# Hauptstation.net
KiCad netlist of a schematic drawn in EAGLE
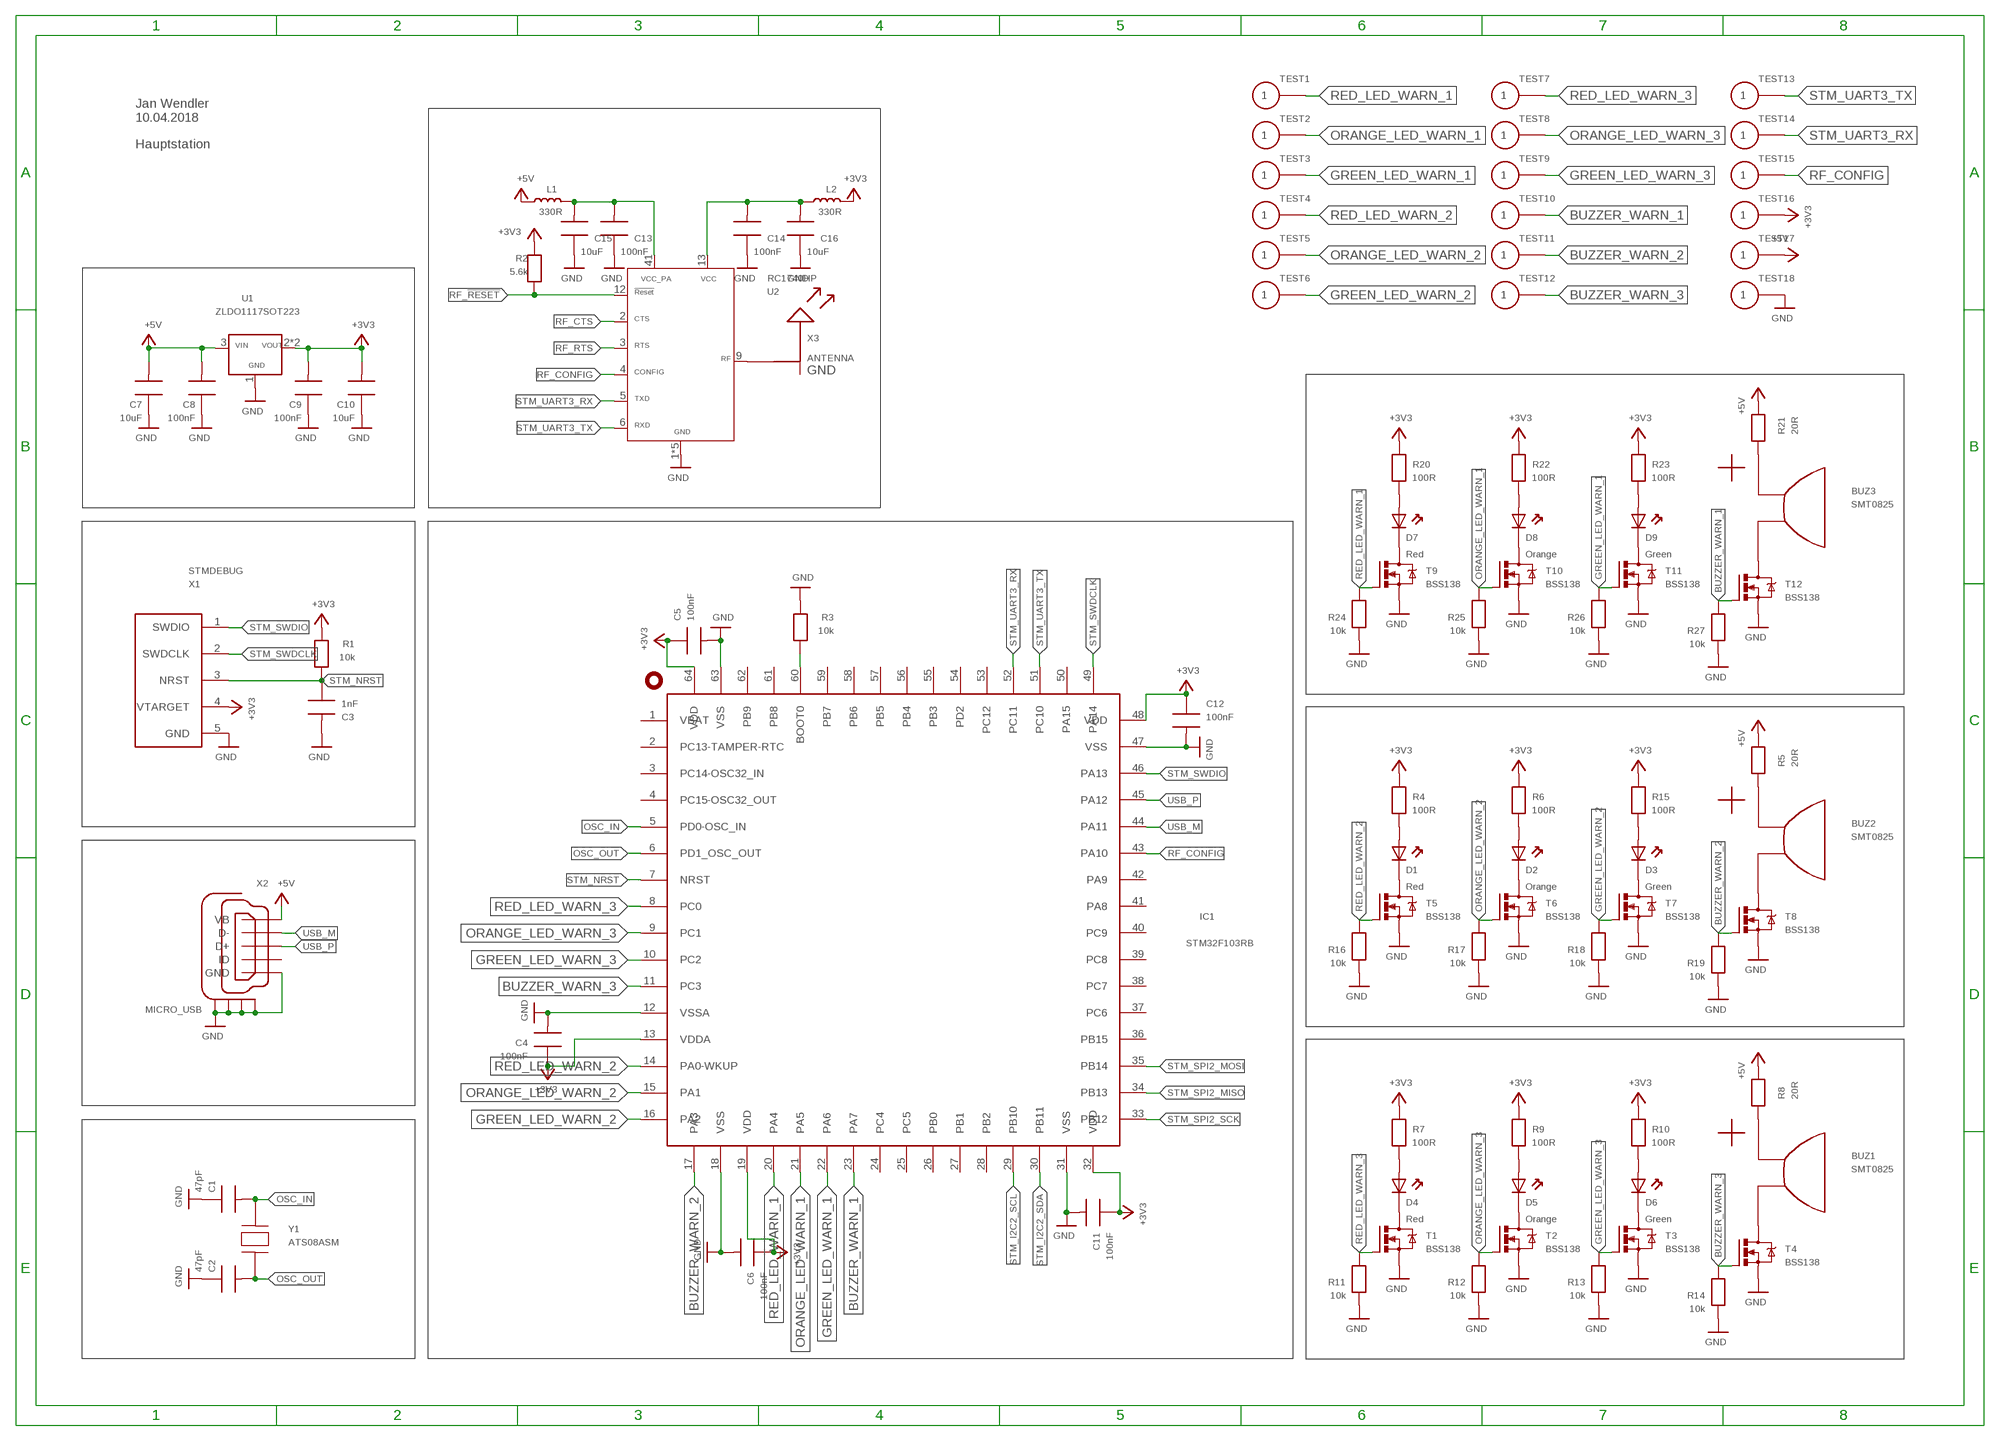
[diagram p0: schematic, sheet 1]

(export (version "E")
  (design (tool "Eeschema 10.0.6"))
  (components
    (comp (ref "BUZ1")
      (value "SMT0825")
      (footprint "eagle-import:SMT0825")
      (libsource (lib "eagle-import") (part "SMT0825"))
    )
    (comp (ref "BUZ2")
      (value "SMT0825")
      (footprint "eagle-import:SMT0825")
      (libsource (lib "eagle-import") (part "SMT0825"))
    )
    (comp (ref "BUZ3")
      (value "SMT0825")
      (footprint "eagle-import:SMT0825")
      (libsource (lib "eagle-import") (part "SMT0825"))
    )
    (comp (ref "C1")
      (value "47pF")
      (footprint "eagle-import:0603")
      (libsource (lib "eagle-import") (part "C0603"))
    )
    (comp (ref "C2")
      (value "47pF")
      (footprint "eagle-import:0603")
      (libsource (lib "eagle-import") (part "C0603"))
    )
    (comp (ref "C3")
      (value "1nF")
      (footprint "eagle-import:0603")
      (libsource (lib "eagle-import") (part "C0603"))
    )
    (comp (ref "C4")
      (value "100nF")
      (footprint "eagle-import:0603")
      (libsource (lib "eagle-import") (part "C0603"))
    )
    (comp (ref "C5")
      (value "100nF")
      (footprint "eagle-import:0603")
      (libsource (lib "eagle-import") (part "C0603"))
    )
    (comp (ref "C6")
      (value "100nF")
      (footprint "eagle-import:0603")
      (libsource (lib "eagle-import") (part "C0603"))
    )
    (comp (ref "C7")
      (value "10uF")
      (footprint "eagle-import:0603")
      (libsource (lib "eagle-import") (part "C0603"))
    )
    (comp (ref "C8")
      (value "100nF")
      (footprint "eagle-import:0603")
      (libsource (lib "eagle-import") (part "C0603"))
    )
    (comp (ref "C9")
      (value "100nF")
      (footprint "eagle-import:0603")
      (libsource (lib "eagle-import") (part "C0603"))
    )
    (comp (ref "C10")
      (value "10uF")
      (footprint "eagle-import:0603")
      (libsource (lib "eagle-import") (part "C0603"))
    )
    (comp (ref "C11")
      (value "100nF")
      (footprint "eagle-import:0603")
      (libsource (lib "eagle-import") (part "C0603"))
    )
    (comp (ref "C12")
      (value "100nF")
      (footprint "eagle-import:0603")
      (libsource (lib "eagle-import") (part "C0603"))
    )
    (comp (ref "C13")
      (value "100nF")
      (footprint "eagle-import:0603")
      (libsource (lib "eagle-import") (part "C0603"))
    )
    (comp (ref "C14")
      (value "100nF")
      (footprint "eagle-import:0603")
      (libsource (lib "eagle-import") (part "C0603"))
    )
    (comp (ref "C15")
      (value "10uF")
      (footprint "eagle-import:0603")
      (libsource (lib "eagle-import") (part "C0603"))
    )
    (comp (ref "C16")
      (value "10uF")
      (footprint "eagle-import:0603")
      (libsource (lib "eagle-import") (part "C0603"))
    )
    (comp (ref "D1")
      (value "Red")
      (footprint "eagle-import:0603")
      (libsource (lib "eagle-import") (part "D0603"))
    )
    (comp (ref "D2")
      (value "Orange")
      (footprint "eagle-import:0603")
      (libsource (lib "eagle-import") (part "D0603"))
    )
    (comp (ref "D3")
      (value "Green")
      (footprint "eagle-import:0603")
      (libsource (lib "eagle-import") (part "D0603"))
    )
    (comp (ref "D4")
      (value "Red")
      (footprint "eagle-import:0603")
      (libsource (lib "eagle-import") (part "D0603"))
    )
    (comp (ref "D5")
      (value "Orange")
      (footprint "eagle-import:0603")
      (libsource (lib "eagle-import") (part "D0603"))
    )
    (comp (ref "D6")
      (value "Green")
      (footprint "eagle-import:0603")
      (libsource (lib "eagle-import") (part "D0603"))
    )
    (comp (ref "D7")
      (value "Red")
      (footprint "eagle-import:0603")
      (libsource (lib "eagle-import") (part "D0603"))
    )
    (comp (ref "D8")
      (value "Orange")
      (footprint "eagle-import:0603")
      (libsource (lib "eagle-import") (part "D0603"))
    )
    (comp (ref "D9")
      (value "Green")
      (footprint "eagle-import:0603")
      (libsource (lib "eagle-import") (part "D0603"))
    )
    (comp (ref "IC1")
      (value "STM32F103RB")
      (footprint "eagle-import:LQFP64")
      (libsource (lib "eagle-import") (part "STM32F103RB"))
    )
    (comp (ref "L1")
      (value "330R")
      (footprint "eagle-import:0603")
      (libsource (lib "eagle-import") (part "L0603"))
    )
    (comp (ref "L2")
      (value "330R")
      (footprint "eagle-import:0603")
      (libsource (lib "eagle-import") (part "L0603"))
    )
    (comp (ref "R1")
      (value "10k")
      (footprint "eagle-import:0603")
      (libsource (lib "eagle-import") (part "R0603"))
    )
    (comp (ref "R2")
      (value "5.6k")
      (footprint "eagle-import:0603")
      (libsource (lib "eagle-import") (part "R0603"))
    )
    (comp (ref "R3")
      (value "10k")
      (footprint "eagle-import:0603")
      (libsource (lib "eagle-import") (part "R0603"))
    )
    (comp (ref "R4")
      (value "100R")
      (footprint "eagle-import:0603")
      (libsource (lib "eagle-import") (part "R0603"))
    )
    (comp (ref "R5")
      (value "20R")
      (footprint "eagle-import:0603")
      (libsource (lib "eagle-import") (part "R0603"))
    )
    (comp (ref "R6")
      (value "100R")
      (footprint "eagle-import:0603")
      (libsource (lib "eagle-import") (part "R0603"))
    )
    (comp (ref "R7")
      (value "100R")
      (footprint "eagle-import:0603")
      (libsource (lib "eagle-import") (part "R0603"))
    )
    (comp (ref "R8")
      (value "20R")
      (footprint "eagle-import:0603")
      (libsource (lib "eagle-import") (part "R0603"))
    )
    (comp (ref "R9")
      (value "100R")
      (footprint "eagle-import:0603")
      (libsource (lib "eagle-import") (part "R0603"))
    )
    (comp (ref "R10")
      (value "100R")
      (footprint "eagle-import:0603")
      (libsource (lib "eagle-import") (part "R0603"))
    )
    (comp (ref "R11")
      (value "10k")
      (footprint "eagle-import:0603")
      (libsource (lib "eagle-import") (part "R0603"))
    )
    (comp (ref "R12")
      (value "10k")
      (footprint "eagle-import:0603")
      (libsource (lib "eagle-import") (part "R0603"))
    )
    (comp (ref "R13")
      (value "10k")
      (footprint "eagle-import:0603")
      (libsource (lib "eagle-import") (part "R0603"))
    )
    (comp (ref "R14")
      (value "10k")
      (footprint "eagle-import:0603")
      (libsource (lib "eagle-import") (part "R0603"))
    )
    (comp (ref "R15")
      (value "100R")
      (footprint "eagle-import:0603")
      (libsource (lib "eagle-import") (part "R0603"))
    )
    (comp (ref "R16")
      (value "10k")
      (footprint "eagle-import:0603")
      (libsource (lib "eagle-import") (part "R0603"))
    )
    (comp (ref "R17")
      (value "10k")
      (footprint "eagle-import:0603")
      (libsource (lib "eagle-import") (part "R0603"))
    )
    (comp (ref "R18")
      (value "10k")
      (footprint "eagle-import:0603")
      (libsource (lib "eagle-import") (part "R0603"))
    )
    (comp (ref "R19")
      (value "10k")
      (footprint "eagle-import:0603")
      (libsource (lib "eagle-import") (part "R0603"))
    )
    (comp (ref "R20")
      (value "100R")
      (footprint "eagle-import:0603")
      (libsource (lib "eagle-import") (part "R0603"))
    )
    (comp (ref "R21")
      (value "20R")
      (footprint "eagle-import:0603")
      (libsource (lib "eagle-import") (part "R0603"))
    )
    (comp (ref "R22")
      (value "100R")
      (footprint "eagle-import:0603")
      (libsource (lib "eagle-import") (part "R0603"))
    )
    (comp (ref "R23")
      (value "100R")
      (footprint "eagle-import:0603")
      (libsource (lib "eagle-import") (part "R0603"))
    )
    (comp (ref "R24")
      (value "10k")
      (footprint "eagle-import:0603")
      (libsource (lib "eagle-import") (part "R0603"))
    )
    (comp (ref "R25")
      (value "10k")
      (footprint "eagle-import:0603")
      (libsource (lib "eagle-import") (part "R0603"))
    )
    (comp (ref "R26")
      (value "10k")
      (footprint "eagle-import:0603")
      (libsource (lib "eagle-import") (part "R0603"))
    )
    (comp (ref "R27")
      (value "10k")
      (footprint "eagle-import:0603")
      (libsource (lib "eagle-import") (part "R0603"))
    )
    (comp (ref "T1")
      (value "BSS138")
      (footprint "eagle-import:SOT23")
      (libsource (lib "eagle-import") (part "BSS138"))
    )
    (comp (ref "T2")
      (value "BSS138")
      (footprint "eagle-import:SOT23")
      (libsource (lib "eagle-import") (part "BSS138"))
    )
    (comp (ref "T3")
      (value "BSS138")
      (footprint "eagle-import:SOT23")
      (libsource (lib "eagle-import") (part "BSS138"))
    )
    (comp (ref "T4")
      (value "BSS138")
      (footprint "eagle-import:SOT23")
      (libsource (lib "eagle-import") (part "BSS138"))
    )
    (comp (ref "T5")
      (value "BSS138")
      (footprint "eagle-import:SOT23")
      (libsource (lib "eagle-import") (part "BSS138"))
    )
    (comp (ref "T6")
      (value "BSS138")
      (footprint "eagle-import:SOT23")
      (libsource (lib "eagle-import") (part "BSS138"))
    )
    (comp (ref "T7")
      (value "BSS138")
      (footprint "eagle-import:SOT23")
      (libsource (lib "eagle-import") (part "BSS138"))
    )
    (comp (ref "T8")
      (value "BSS138")
      (footprint "eagle-import:SOT23")
      (libsource (lib "eagle-import") (part "BSS138"))
    )
    (comp (ref "T9")
      (value "BSS138")
      (footprint "eagle-import:SOT23")
      (libsource (lib "eagle-import") (part "BSS138"))
    )
    (comp (ref "T10")
      (value "BSS138")
      (footprint "eagle-import:SOT23")
      (libsource (lib "eagle-import") (part "BSS138"))
    )
    (comp (ref "T11")
      (value "BSS138")
      (footprint "eagle-import:SOT23")
      (libsource (lib "eagle-import") (part "BSS138"))
    )
    (comp (ref "T12")
      (value "BSS138")
      (footprint "eagle-import:SOT23")
      (libsource (lib "eagle-import") (part "BSS138"))
    )
    (comp (ref "TEST1")
      (value "TESTPIN")
      (footprint "eagle-import:TESTPIN")
      (libsource (lib "eagle-import") (part "TESTPIN"))
    )
    (comp (ref "TEST2")
      (value "TESTPIN")
      (footprint "eagle-import:TESTPIN")
      (libsource (lib "eagle-import") (part "TESTPIN"))
    )
    (comp (ref "TEST3")
      (value "TESTPIN")
      (footprint "eagle-import:TESTPIN")
      (libsource (lib "eagle-import") (part "TESTPIN"))
    )
    (comp (ref "TEST4")
      (value "TESTPIN")
      (footprint "eagle-import:TESTPIN")
      (libsource (lib "eagle-import") (part "TESTPIN"))
    )
    (comp (ref "TEST5")
      (value "TESTPIN")
      (footprint "eagle-import:TESTPIN")
      (libsource (lib "eagle-import") (part "TESTPIN"))
    )
    (comp (ref "TEST6")
      (value "TESTPIN")
      (footprint "eagle-import:TESTPIN")
      (libsource (lib "eagle-import") (part "TESTPIN"))
    )
    (comp (ref "TEST7")
      (value "TESTPIN")
      (footprint "eagle-import:TESTPIN")
      (libsource (lib "eagle-import") (part "TESTPIN"))
    )
    (comp (ref "TEST8")
      (value "TESTPIN")
      (footprint "eagle-import:TESTPIN")
      (libsource (lib "eagle-import") (part "TESTPIN"))
    )
    (comp (ref "TEST9")
      (value "TESTPIN")
      (footprint "eagle-import:TESTPIN")
      (libsource (lib "eagle-import") (part "TESTPIN"))
    )
    (comp (ref "TEST10")
      (value "TESTPIN")
      (footprint "eagle-import:TESTPIN")
      (libsource (lib "eagle-import") (part "TESTPIN"))
    )
    (comp (ref "TEST11")
      (value "TESTPIN")
      (footprint "eagle-import:TESTPIN")
      (libsource (lib "eagle-import") (part "TESTPIN"))
    )
    (comp (ref "TEST12")
      (value "TESTPIN")
      (footprint "eagle-import:TESTPIN")
      (libsource (lib "eagle-import") (part "TESTPIN"))
    )
    (comp (ref "TEST13")
      (value "TESTPIN")
      (footprint "eagle-import:TESTPIN")
      (libsource (lib "eagle-import") (part "TESTPIN"))
    )
    (comp (ref "TEST14")
      (value "TESTPIN")
      (footprint "eagle-import:TESTPIN")
      (libsource (lib "eagle-import") (part "TESTPIN"))
    )
    (comp (ref "TEST15")
      (value "TESTPIN")
      (footprint "eagle-import:TESTPIN")
      (libsource (lib "eagle-import") (part "TESTPIN"))
    )
    (comp (ref "TEST16")
      (value "TESTPIN")
      (footprint "eagle-import:TESTPIN")
      (libsource (lib "eagle-import") (part "TESTPIN"))
    )
    (comp (ref "TEST17")
      (value "TESTPIN")
      (footprint "eagle-import:TESTPIN")
      (libsource (lib "eagle-import") (part "TESTPIN"))
    )
    (comp (ref "TEST18")
      (value "TESTPIN")
      (footprint "eagle-import:TESTPIN")
      (libsource (lib "eagle-import") (part "TESTPIN"))
    )
    (comp (ref "U1")
      (value "ZLDO1117SOT223")
      (footprint "eagle-import:SOT223")
      (libsource (lib "eagle-import") (part "ZLDO1117SOT223"))
    )
    (comp (ref "U2")
      (value "RC1740HP")
      (footprint "eagle-import:RADIOCRAFTS_MODULE")
      (libsource (lib "eagle-import") (part "RC1740HP"))
    )
    (comp (ref "X1")
      (value "STMDEBUG")
      (footprint "eagle-import:STIFTLEISTE1X5")
      (libsource (lib "eagle-import") (part "STMDEBUG"))
    )
    (comp (ref "X2")
      (value "MICRO_USB")
      (footprint "eagle-import:MICRO-USB")
      (libsource (lib "eagle-import") (part "MICRO_USB"))
    )
    (comp (ref "X3")
      (value "ANTENNA")
      (footprint "eagle-import:ANTENNE_CON")
      (libsource (lib "eagle-import") (part "ANTENNA"))
    )
    (comp (ref "Y1")
      (value "ATS08ASM")
      (footprint "eagle-import:HC49_US")
      (libsource (lib "eagle-import") (part "ATS08ASM"))
    )
  )
  (nets
    (net (code "1") (name "+3V3") (class "Default")
      (node (ref "C10") (pin "1") (pinfunction "P$1_1") (pintype "bidirectional"))
      (node (ref "C11") (pin "2") (pinfunction "P$2_2") (pintype "bidirectional"))
      (node (ref "C12") (pin "2") (pinfunction "P$2_2") (pintype "bidirectional"))
      (node (ref "C4") (pin "2") (pinfunction "P$2_2") (pintype "bidirectional"))
      (node (ref "C5") (pin "2") (pinfunction "P$2_2") (pintype "bidirectional"))
      (node (ref "C6") (pin "2") (pinfunction "P$2_2") (pintype "bidirectional"))
      (node (ref "C9") (pin "1") (pinfunction "P$1_1") (pintype "bidirectional"))
      (node (ref "IC1") (pin "13") (pinfunction "VDDA_13") (pintype "bidirectional"))
      (node (ref "IC1") (pin "19") (pinfunction "VDD_19") (pintype "bidirectional"))
      (node (ref "IC1") (pin "32") (pinfunction "VDD_32") (pintype "bidirectional"))
      (node (ref "IC1") (pin "48") (pinfunction "VDD_48") (pintype "bidirectional"))
      (node (ref "IC1") (pin "64") (pinfunction "VDD_64") (pintype "bidirectional"))
      (node (ref "L2") (pin "1") (pinfunction "P$1_1") (pintype "bidirectional"))
      (node (ref "R1") (pin "2") (pinfunction "P$2_2") (pintype "bidirectional"))
      (node (ref "R10") (pin "2") (pinfunction "P$2_2") (pintype "bidirectional"))
      (node (ref "R15") (pin "2") (pinfunction "P$2_2") (pintype "bidirectional"))
      (node (ref "R2") (pin "2") (pinfunction "P$2_2") (pintype "bidirectional"))
      (node (ref "R20") (pin "2") (pinfunction "P$2_2") (pintype "bidirectional"))
      (node (ref "R22") (pin "2") (pinfunction "P$2_2") (pintype "bidirectional"))
      (node (ref "R23") (pin "2") (pinfunction "P$2_2") (pintype "bidirectional"))
      (node (ref "R4") (pin "2") (pinfunction "P$2_2") (pintype "bidirectional"))
      (node (ref "R6") (pin "2") (pinfunction "P$2_2") (pintype "bidirectional"))
      (node (ref "R7") (pin "2") (pinfunction "P$2_2") (pintype "bidirectional"))
      (node (ref "R9") (pin "2") (pinfunction "P$2_2") (pintype "bidirectional"))
      (node (ref "TEST16") (pin "1") (pinfunction "1_1") (pintype "bidirectional"))
      (node (ref "U1") (pin "2") (pinfunction "VOUT_2") (pintype "bidirectional"))
      (node (ref "U1") (pin "PAD") (pinfunction "VOUT_PAD") (pintype "bidirectional"))
      (node (ref "X1") (pin "4") (pinfunction "VTARGET_4") (pintype "bidirectional"))
    )
    (net (code "2") (name "+5V") (class "Default")
      (node (ref "C7") (pin "1") (pinfunction "P$1_1") (pintype "bidirectional"))
      (node (ref "C8") (pin "1") (pinfunction "P$1_1") (pintype "bidirectional"))
      (node (ref "L1") (pin "2") (pinfunction "P$2_2") (pintype "bidirectional"))
      (node (ref "R21") (pin "2") (pinfunction "P$2_2") (pintype "bidirectional"))
      (node (ref "R5") (pin "2") (pinfunction "P$2_2") (pintype "bidirectional"))
      (node (ref "R8") (pin "2") (pinfunction "P$2_2") (pintype "bidirectional"))
      (node (ref "TEST17") (pin "1") (pinfunction "1_1") (pintype "bidirectional"))
      (node (ref "U1") (pin "3") (pinfunction "VIN_3") (pintype "bidirectional"))
      (node (ref "X2") (pin "1") (pinfunction "VB_1") (pintype "passive"))
    )
    (net (code "3") (name "/RF_~{RESET}") (class "Default")
      (node (ref "R2") (pin "1") (pinfunction "P$1_1") (pintype "bidirectional"))
      (node (ref "U2") (pin "12") (pinfunction "~{RESET}_12") (pintype "bidirectional"))
    )
    (net (code "4") (name "BUZZER_WARN_1") (class "Default")
      (node (ref "IC1") (pin "23") (pinfunction "PA7_23") (pintype "bidirectional"))
      (node (ref "R27") (pin "2") (pinfunction "P$2_2") (pintype "bidirectional"))
      (node (ref "T12") (pin "1") (pinfunction "G_1") (pintype "passive"))
      (node (ref "TEST10") (pin "1") (pinfunction "1_1") (pintype "bidirectional"))
    )
    (net (code "5") (name "BUZZER_WARN_2") (class "Default")
      (node (ref "IC1") (pin "17") (pinfunction "PA3_17") (pintype "bidirectional"))
      (node (ref "R19") (pin "2") (pinfunction "P$2_2") (pintype "bidirectional"))
      (node (ref "T8") (pin "1") (pinfunction "G_1") (pintype "passive"))
      (node (ref "TEST11") (pin "1") (pinfunction "1_1") (pintype "bidirectional"))
    )
    (net (code "6") (name "BUZZER_WARN_3") (class "Default")
      (node (ref "IC1") (pin "11") (pinfunction "PC3_11") (pintype "bidirectional"))
      (node (ref "R14") (pin "2") (pinfunction "P$2_2") (pintype "bidirectional"))
      (node (ref "T4") (pin "1") (pinfunction "G_1") (pintype "passive"))
      (node (ref "TEST12") (pin "1") (pinfunction "1_1") (pintype "bidirectional"))
    )
    (net (code "7") (name "GND") (class "Default")
      (node (ref "C1") (pin "2") (pinfunction "P$2_2") (pintype "bidirectional"))
      (node (ref "C10") (pin "2") (pinfunction "P$2_2") (pintype "bidirectional"))
      (node (ref "C11") (pin "1") (pinfunction "P$1_1") (pintype "bidirectional"))
      (node (ref "C12") (pin "1") (pinfunction "P$1_1") (pintype "bidirectional"))
      (node (ref "C13") (pin "2") (pinfunction "P$2_2") (pintype "bidirectional"))
      (node (ref "C14") (pin "2") (pinfunction "P$2_2") (pintype "bidirectional"))
      (node (ref "C15") (pin "2") (pinfunction "P$2_2") (pintype "bidirectional"))
      (node (ref "C16") (pin "2") (pinfunction "P$2_2") (pintype "bidirectional"))
      (node (ref "C2") (pin "2") (pinfunction "P$2_2") (pintype "bidirectional"))
      (node (ref "C3") (pin "1") (pinfunction "P$1_1") (pintype "bidirectional"))
      (node (ref "C4") (pin "1") (pinfunction "P$1_1") (pintype "bidirectional"))
      (node (ref "C5") (pin "1") (pinfunction "P$1_1") (pintype "bidirectional"))
      (node (ref "C6") (pin "1") (pinfunction "P$1_1") (pintype "bidirectional"))
      (node (ref "C7") (pin "2") (pinfunction "P$2_2") (pintype "bidirectional"))
      (node (ref "C8") (pin "2") (pinfunction "P$2_2") (pintype "bidirectional"))
      (node (ref "C9") (pin "2") (pinfunction "P$2_2") (pintype "bidirectional"))
      (node (ref "IC1") (pin "12") (pinfunction "VSSA_12") (pintype "bidirectional"))
      (node (ref "IC1") (pin "18") (pinfunction "VSS_18") (pintype "bidirectional"))
      (node (ref "IC1") (pin "31") (pinfunction "VSS_31") (pintype "bidirectional"))
      (node (ref "IC1") (pin "47") (pinfunction "VSS_47") (pintype "bidirectional"))
      (node (ref "IC1") (pin "63") (pinfunction "VSS_63") (pintype "bidirectional"))
      (node (ref "R11") (pin "1") (pinfunction "P$1_1") (pintype "bidirectional"))
      (node (ref "R12") (pin "1") (pinfunction "P$1_1") (pintype "bidirectional"))
      (node (ref "R13") (pin "1") (pinfunction "P$1_1") (pintype "bidirectional"))
      (node (ref "R14") (pin "1") (pinfunction "P$1_1") (pintype "bidirectional"))
      (node (ref "R16") (pin "1") (pinfunction "P$1_1") (pintype "bidirectional"))
      (node (ref "R17") (pin "1") (pinfunction "P$1_1") (pintype "bidirectional"))
      (node (ref "R18") (pin "1") (pinfunction "P$1_1") (pintype "bidirectional"))
      (node (ref "R19") (pin "1") (pinfunction "P$1_1") (pintype "bidirectional"))
      (node (ref "R24") (pin "1") (pinfunction "P$1_1") (pintype "bidirectional"))
      (node (ref "R25") (pin "1") (pinfunction "P$1_1") (pintype "bidirectional"))
      (node (ref "R26") (pin "1") (pinfunction "P$1_1") (pintype "bidirectional"))
      (node (ref "R27") (pin "1") (pinfunction "P$1_1") (pintype "bidirectional"))
      (node (ref "R3") (pin "2") (pinfunction "P$2_2") (pintype "bidirectional"))
      (node (ref "T1") (pin "2") (pinfunction "S_2") (pintype "passive"))
      (node (ref "T10") (pin "2") (pinfunction "S_2") (pintype "passive"))
      (node (ref "T11") (pin "2") (pinfunction "S_2") (pintype "passive"))
      (node (ref "T12") (pin "2") (pinfunction "S_2") (pintype "passive"))
      (node (ref "T2") (pin "2") (pinfunction "S_2") (pintype "passive"))
      (node (ref "T3") (pin "2") (pinfunction "S_2") (pintype "passive"))
      (node (ref "T4") (pin "2") (pinfunction "S_2") (pintype "passive"))
      (node (ref "T5") (pin "2") (pinfunction "S_2") (pintype "passive"))
      (node (ref "T6") (pin "2") (pinfunction "S_2") (pintype "passive"))
      (node (ref "T7") (pin "2") (pinfunction "S_2") (pintype "passive"))
      (node (ref "T8") (pin "2") (pinfunction "S_2") (pintype "passive"))
      (node (ref "T9") (pin "2") (pinfunction "S_2") (pintype "passive"))
      (node (ref "TEST18") (pin "1") (pinfunction "1_1") (pintype "bidirectional"))
      (node (ref "U1") (pin "1") (pinfunction "GND_1") (pintype "bidirectional"))
      (node (ref "U2") (pin "1") (pinfunction "GND_1") (pintype "bidirectional"))
      (node (ref "U2") (pin "10") (pinfunction "GND_10") (pintype "bidirectional"))
      (node (ref "U2") (pin "14") (pinfunction "GND_14") (pintype "bidirectional"))
      (node (ref "U2") (pin "7") (pinfunction "GND_7") (pintype "bidirectional"))
      (node (ref "U2") (pin "8") (pinfunction "GND_8") (pintype "bidirectional"))
      (node (ref "X1") (pin "5") (pinfunction "GND_5") (pintype "bidirectional"))
      (node (ref "X2") (pin "5") (pinfunction "GND_5") (pintype "passive"))
      (node (ref "X2") (pin "GND1") (pinfunction "S1_GND1") (pintype "passive"))
      (node (ref "X2") (pin "GND2") (pinfunction "S2_GND2") (pintype "passive"))
      (node (ref "X2") (pin "GND3") (pinfunction "S3_GND3") (pintype "passive"))
      (node (ref "X2") (pin "GND4") (pinfunction "S4_GND4") (pintype "passive"))
    )
    (net (code "8") (name "GREEN_LED_WARN_1") (class "Default")
      (node (ref "IC1") (pin "22") (pinfunction "PA6_22") (pintype "bidirectional"))
      (node (ref "R26") (pin "2") (pinfunction "P$2_2") (pintype "bidirectional"))
      (node (ref "T11") (pin "1") (pinfunction "G_1") (pintype "passive"))
      (node (ref "TEST3") (pin "1") (pinfunction "1_1") (pintype "bidirectional"))
    )
    (net (code "9") (name "GREEN_LED_WARN_2") (class "Default")
      (node (ref "IC1") (pin "16") (pinfunction "PA2_16") (pintype "bidirectional"))
      (node (ref "R18") (pin "2") (pinfunction "P$2_2") (pintype "bidirectional"))
      (node (ref "T7") (pin "1") (pinfunction "G_1") (pintype "passive"))
      (node (ref "TEST6") (pin "1") (pinfunction "1_1") (pintype "bidirectional"))
    )
    (net (code "10") (name "GREEN_LED_WARN_3") (class "Default")
      (node (ref "IC1") (pin "10") (pinfunction "PC2_10") (pintype "bidirectional"))
      (node (ref "R13") (pin "2") (pinfunction "P$2_2") (pintype "bidirectional"))
      (node (ref "T3") (pin "1") (pinfunction "G_1") (pintype "passive"))
      (node (ref "TEST9") (pin "1") (pinfunction "1_1") (pintype "bidirectional"))
    )
    (net (code "11") (name "Net-(BUZ1-P$1)") (class "Default")
      (node (ref "BUZ1") (pin "+") (pinfunction "P$1_+") (pintype "bidirectional"))
      (node (ref "R8") (pin "1") (pinfunction "P$1_1") (pintype "bidirectional"))
    )
    (net (code "12") (name "Net-(BUZ1-P$2)") (class "Default")
      (node (ref "BUZ1") (pin "-") (pinfunction "P$2_-") (pintype "bidirectional"))
      (node (ref "T4") (pin "3") (pinfunction "D_3") (pintype "passive"))
    )
    (net (code "13") (name "Net-(BUZ2-P$1)") (class "Default")
      (node (ref "BUZ2") (pin "+") (pinfunction "P$1_+") (pintype "bidirectional"))
      (node (ref "R5") (pin "1") (pinfunction "P$1_1") (pintype "bidirectional"))
    )
    (net (code "14") (name "Net-(BUZ2-P$2)") (class "Default")
      (node (ref "BUZ2") (pin "-") (pinfunction "P$2_-") (pintype "bidirectional"))
      (node (ref "T8") (pin "3") (pinfunction "D_3") (pintype "passive"))
    )
    (net (code "15") (name "Net-(BUZ3-P$1)") (class "Default")
      (node (ref "BUZ3") (pin "+") (pinfunction "P$1_+") (pintype "bidirectional"))
      (node (ref "R21") (pin "1") (pinfunction "P$1_1") (pintype "bidirectional"))
    )
    (net (code "16") (name "Net-(BUZ3-P$2)") (class "Default")
      (node (ref "BUZ3") (pin "-") (pinfunction "P$2_-") (pintype "bidirectional"))
      (node (ref "T12") (pin "3") (pinfunction "D_3") (pintype "passive"))
    )
    (net (code "17") (name "Net-(C13-P$1)") (class "Default")
      (node (ref "C13") (pin "1") (pinfunction "P$1_1") (pintype "bidirectional"))
      (node (ref "C15") (pin "1") (pinfunction "P$1_1") (pintype "bidirectional"))
      (node (ref "L1") (pin "1") (pinfunction "P$1_1") (pintype "bidirectional"))
      (node (ref "U2") (pin "41") (pinfunction "VCC_PA_41") (pintype "bidirectional"))
    )
    (net (code "18") (name "Net-(C14-P$1)") (class "Default")
      (node (ref "C14") (pin "1") (pinfunction "P$1_1") (pintype "bidirectional"))
      (node (ref "C16") (pin "1") (pinfunction "P$1_1") (pintype "bidirectional"))
      (node (ref "L2") (pin "2") (pinfunction "P$2_2") (pintype "bidirectional"))
      (node (ref "U2") (pin "13") (pinfunction "VCC_13") (pintype "bidirectional"))
    )
    (net (code "19") (name "Net-(D1-ANODE)") (class "Default")
      (node (ref "D1") (pin "1") (pinfunction "ANODE_1") (pintype "bidirectional"))
      (node (ref "R4") (pin "1") (pinfunction "P$1_1") (pintype "bidirectional"))
    )
    (net (code "20") (name "Net-(D1-KATHODE)") (class "Default")
      (node (ref "D1") (pin "2") (pinfunction "KATHODE_2") (pintype "bidirectional"))
      (node (ref "T5") (pin "3") (pinfunction "D_3") (pintype "passive"))
    )
    (net (code "21") (name "Net-(D2-ANODE)") (class "Default")
      (node (ref "D2") (pin "1") (pinfunction "ANODE_1") (pintype "bidirectional"))
      (node (ref "R6") (pin "1") (pinfunction "P$1_1") (pintype "bidirectional"))
    )
    (net (code "22") (name "Net-(D2-KATHODE)") (class "Default")
      (node (ref "D2") (pin "2") (pinfunction "KATHODE_2") (pintype "bidirectional"))
      (node (ref "T6") (pin "3") (pinfunction "D_3") (pintype "passive"))
    )
    (net (code "23") (name "Net-(D3-ANODE)") (class "Default")
      (node (ref "D3") (pin "1") (pinfunction "ANODE_1") (pintype "bidirectional"))
      (node (ref "R15") (pin "1") (pinfunction "P$1_1") (pintype "bidirectional"))
    )
    (net (code "24") (name "Net-(D3-KATHODE)") (class "Default")
      (node (ref "D3") (pin "2") (pinfunction "KATHODE_2") (pintype "bidirectional"))
      (node (ref "T7") (pin "3") (pinfunction "D_3") (pintype "passive"))
    )
    (net (code "25") (name "Net-(D4-ANODE)") (class "Default")
      (node (ref "D4") (pin "1") (pinfunction "ANODE_1") (pintype "bidirectional"))
      (node (ref "R7") (pin "1") (pinfunction "P$1_1") (pintype "bidirectional"))
    )
    (net (code "26") (name "Net-(D4-KATHODE)") (class "Default")
      (node (ref "D4") (pin "2") (pinfunction "KATHODE_2") (pintype "bidirectional"))
      (node (ref "T1") (pin "3") (pinfunction "D_3") (pintype "passive"))
    )
    (net (code "27") (name "Net-(D5-ANODE)") (class "Default")
      (node (ref "D5") (pin "1") (pinfunction "ANODE_1") (pintype "bidirectional"))
      (node (ref "R9") (pin "1") (pinfunction "P$1_1") (pintype "bidirectional"))
    )
    (net (code "28") (name "Net-(D5-KATHODE)") (class "Default")
      (node (ref "D5") (pin "2") (pinfunction "KATHODE_2") (pintype "bidirectional"))
      (node (ref "T2") (pin "3") (pinfunction "D_3") (pintype "passive"))
    )
    (net (code "29") (name "Net-(D6-ANODE)") (class "Default")
      (node (ref "D6") (pin "1") (pinfunction "ANODE_1") (pintype "bidirectional"))
      (node (ref "R10") (pin "1") (pinfunction "P$1_1") (pintype "bidirectional"))
    )
    (net (code "30") (name "Net-(D6-KATHODE)") (class "Default")
      (node (ref "D6") (pin "2") (pinfunction "KATHODE_2") (pintype "bidirectional"))
      (node (ref "T3") (pin "3") (pinfunction "D_3") (pintype "passive"))
    )
    (net (code "31") (name "Net-(D7-ANODE)") (class "Default")
      (node (ref "D7") (pin "1") (pinfunction "ANODE_1") (pintype "bidirectional"))
      (node (ref "R20") (pin "1") (pinfunction "P$1_1") (pintype "bidirectional"))
    )
    (net (code "32") (name "Net-(D7-KATHODE)") (class "Default")
      (node (ref "D7") (pin "2") (pinfunction "KATHODE_2") (pintype "bidirectional"))
      (node (ref "T9") (pin "3") (pinfunction "D_3") (pintype "passive"))
    )
    (net (code "33") (name "Net-(D8-ANODE)") (class "Default")
      (node (ref "D8") (pin "1") (pinfunction "ANODE_1") (pintype "bidirectional"))
      (node (ref "R22") (pin "1") (pinfunction "P$1_1") (pintype "bidirectional"))
    )
    (net (code "34") (name "Net-(D8-KATHODE)") (class "Default")
      (node (ref "D8") (pin "2") (pinfunction "KATHODE_2") (pintype "bidirectional"))
      (node (ref "T10") (pin "3") (pinfunction "D_3") (pintype "passive"))
    )
    (net (code "35") (name "Net-(D9-ANODE)") (class "Default")
      (node (ref "D9") (pin "1") (pinfunction "ANODE_1") (pintype "bidirectional"))
      (node (ref "R23") (pin "1") (pinfunction "P$1_1") (pintype "bidirectional"))
    )
    (net (code "36") (name "Net-(D9-KATHODE)") (class "Default")
      (node (ref "D9") (pin "2") (pinfunction "KATHODE_2") (pintype "bidirectional"))
      (node (ref "T11") (pin "3") (pinfunction "D_3") (pintype "passive"))
    )
    (net (code "37") (name "Net-(IC1-BOOT0)") (class "Default")
      (node (ref "IC1") (pin "60") (pinfunction "BOOT0_60") (pintype "bidirectional"))
      (node (ref "R3") (pin "1") (pinfunction "P$1_1") (pintype "bidirectional"))
    )
    (net (code "38") (name "Net-(U2-RF)") (class "Default")
      (node (ref "U2") (pin "9") (pinfunction "RF_9") (pintype "bidirectional"))
      (node (ref "X3") (pin "P$1") (pinfunction "P$1_P$1") (pintype "bidirectional"))
    )
    (net (code "39") (name "ORANGE_LED_WARN_1") (class "Default")
      (node (ref "IC1") (pin "21") (pinfunction "PA5_21") (pintype "bidirectional"))
      (node (ref "R25") (pin "2") (pinfunction "P$2_2") (pintype "bidirectional"))
      (node (ref "T10") (pin "1") (pinfunction "G_1") (pintype "passive"))
      (node (ref "TEST2") (pin "1") (pinfunction "1_1") (pintype "bidirectional"))
    )
    (net (code "40") (name "ORANGE_LED_WARN_2") (class "Default")
      (node (ref "IC1") (pin "15") (pinfunction "PA1_15") (pintype "bidirectional"))
      (node (ref "R17") (pin "2") (pinfunction "P$2_2") (pintype "bidirectional"))
      (node (ref "T6") (pin "1") (pinfunction "G_1") (pintype "passive"))
      (node (ref "TEST5") (pin "1") (pinfunction "1_1") (pintype "bidirectional"))
    )
    (net (code "41") (name "ORANGE_LED_WARN_3") (class "Default")
      (node (ref "IC1") (pin "9") (pinfunction "PC1_9") (pintype "bidirectional"))
      (node (ref "R12") (pin "2") (pinfunction "P$2_2") (pintype "bidirectional"))
      (node (ref "T2") (pin "1") (pinfunction "G_1") (pintype "passive"))
      (node (ref "TEST8") (pin "1") (pinfunction "1_1") (pintype "bidirectional"))
    )
    (net (code "42") (name "OSC_IN") (class "Default")
      (node (ref "C1") (pin "1") (pinfunction "P$1_1") (pintype "bidirectional"))
      (node (ref "IC1") (pin "5") (pinfunction "PD0-OSC_IN_5") (pintype "bidirectional"))
      (node (ref "Y1") (pin "1") (pinfunction "P$1_1") (pintype "bidirectional"))
    )
    (net (code "43") (name "OSC_OUT") (class "Default")
      (node (ref "C2") (pin "1") (pinfunction "P$1_1") (pintype "bidirectional"))
      (node (ref "IC1") (pin "6") (pinfunction "PD1_OSC_OUT_6") (pintype "bidirectional"))
      (node (ref "Y1") (pin "2") (pinfunction "P$2_2") (pintype "bidirectional"))
    )
    (net (code "44") (name "RED_LED_WARN_1") (class "Default")
      (node (ref "IC1") (pin "20") (pinfunction "PA4_20") (pintype "bidirectional"))
      (node (ref "R24") (pin "2") (pinfunction "P$2_2") (pintype "bidirectional"))
      (node (ref "T9") (pin "1") (pinfunction "G_1") (pintype "passive"))
      (node (ref "TEST1") (pin "1") (pinfunction "1_1") (pintype "bidirectional"))
    )
    (net (code "45") (name "RED_LED_WARN_2") (class "Default")
      (node (ref "IC1") (pin "14") (pinfunction "PA0-WKUP_14") (pintype "bidirectional"))
      (node (ref "R16") (pin "2") (pinfunction "P$2_2") (pintype "bidirectional"))
      (node (ref "T5") (pin "1") (pinfunction "G_1") (pintype "passive"))
      (node (ref "TEST4") (pin "1") (pinfunction "1_1") (pintype "bidirectional"))
    )
    (net (code "46") (name "RED_LED_WARN_3") (class "Default")
      (node (ref "IC1") (pin "8") (pinfunction "PC0_8") (pintype "bidirectional"))
      (node (ref "R11") (pin "2") (pinfunction "P$2_2") (pintype "bidirectional"))
      (node (ref "T1") (pin "1") (pinfunction "G_1") (pintype "passive"))
      (node (ref "TEST7") (pin "1") (pinfunction "1_1") (pintype "bidirectional"))
    )
    (net (code "47") (name "RF_CONFIG") (class "Default")
      (node (ref "IC1") (pin "43") (pinfunction "PA10_43") (pintype "bidirectional"))
      (node (ref "TEST15") (pin "1") (pinfunction "1_1") (pintype "bidirectional"))
      (node (ref "U2") (pin "4") (pinfunction "CONFIG_4") (pintype "bidirectional"))
    )
    (net (code "48") (name "RF_CTS") (class "Default")
      (node (ref "U2") (pin "2") (pinfunction "CTS_2") (pintype "bidirectional"))
    )
    (net (code "49") (name "RF_RTS") (class "Default")
      (node (ref "U2") (pin "3") (pinfunction "RTS_3") (pintype "bidirectional"))
    )
    (net (code "50") (name "STM_I2C2_SCL") (class "Default")
      (node (ref "IC1") (pin "29") (pinfunction "PB10_29") (pintype "bidirectional"))
    )
    (net (code "51") (name "STM_I2C2_SDA") (class "Default")
      (node (ref "IC1") (pin "30") (pinfunction "PB11_30") (pintype "bidirectional"))
    )
    (net (code "52") (name "STM_NRST") (class "Default")
      (node (ref "C3") (pin "2") (pinfunction "P$2_2") (pintype "bidirectional"))
      (node (ref "IC1") (pin "7") (pinfunction "NRST_7") (pintype "bidirectional"))
      (node (ref "R1") (pin "1") (pinfunction "P$1_1") (pintype "bidirectional"))
      (node (ref "X1") (pin "3") (pinfunction "NRST_3") (pintype "bidirectional"))
    )
    (net (code "53") (name "STM_SPI2_MISO") (class "Default")
      (node (ref "IC1") (pin "34") (pinfunction "PB13_34") (pintype "bidirectional"))
    )
    (net (code "54") (name "STM_SPI2_MOSI") (class "Default")
      (node (ref "IC1") (pin "35") (pinfunction "PB14_35") (pintype "bidirectional"))
    )
    (net (code "55") (name "STM_SPI2_SCK") (class "Default")
      (node (ref "IC1") (pin "33") (pinfunction "PB12_33") (pintype "bidirectional"))
    )
    (net (code "56") (name "STM_SWDCLK") (class "Default")
      (node (ref "IC1") (pin "49") (pinfunction "PA14_49") (pintype "bidirectional"))
      (node (ref "X1") (pin "2") (pinfunction "SWDCLK_2") (pintype "bidirectional"))
    )
    (net (code "57") (name "STM_SWDIO") (class "Default")
      (node (ref "IC1") (pin "46") (pinfunction "PA13_46") (pintype "bidirectional"))
      (node (ref "X1") (pin "1") (pinfunction "SWDIO_1") (pintype "bidirectional"))
    )
    (net (code "58") (name "STM_UART3_RX") (class "Default")
      (node (ref "IC1") (pin "52") (pinfunction "PC11_52") (pintype "bidirectional"))
      (node (ref "TEST14") (pin "1") (pinfunction "1_1") (pintype "bidirectional"))
      (node (ref "U2") (pin "5") (pinfunction "TXD_5") (pintype "bidirectional"))
    )
    (net (code "59") (name "STM_UART3_TX") (class "Default")
      (node (ref "IC1") (pin "51") (pinfunction "PC10_51") (pintype "bidirectional"))
      (node (ref "TEST13") (pin "1") (pinfunction "1_1") (pintype "bidirectional"))
      (node (ref "U2") (pin "6") (pinfunction "RXD_6") (pintype "bidirectional"))
    )
    (net (code "60") (name "USB_M") (class "Default")
      (node (ref "IC1") (pin "44") (pinfunction "PA11_44") (pintype "bidirectional"))
      (node (ref "X2") (pin "2") (pinfunction "D-_2") (pintype "passive"))
    )
    (net (code "61") (name "USB_P") (class "Default")
      (node (ref "IC1") (pin "45") (pinfunction "PA12_45") (pintype "bidirectional"))
      (node (ref "X2") (pin "3") (pinfunction "D+_3") (pintype "passive"))
    )
    (net (code "62") (name "unconnected-(IC1-PA8-Pad41)") (class "Default")
      (node (ref "IC1") (pin "41") (pinfunction "PA8_41") (pintype "bidirectional"))
    )
    (net (code "63") (name "unconnected-(IC1-PA9-Pad42)") (class "Default")
      (node (ref "IC1") (pin "42") (pinfunction "PA9_42") (pintype "bidirectional"))
    )
    (net (code "64") (name "unconnected-(IC1-PA15-Pad50)") (class "Default")
      (node (ref "IC1") (pin "50") (pinfunction "PA15_50") (pintype "bidirectional"))
    )
    (net (code "65") (name "unconnected-(IC1-PB0-Pad26)") (class "Default")
      (node (ref "IC1") (pin "26") (pinfunction "PB0_26") (pintype "bidirectional"))
    )
    (net (code "66") (name "unconnected-(IC1-PB1-Pad27)") (class "Default")
      (node (ref "IC1") (pin "27") (pinfunction "PB1_27") (pintype "bidirectional"))
    )
    (net (code "67") (name "unconnected-(IC1-PB2-Pad28)") (class "Default")
      (node (ref "IC1") (pin "28") (pinfunction "PB2_28") (pintype "bidirectional"))
    )
    (net (code "68") (name "unconnected-(IC1-PB3-Pad55)") (class "Default")
      (node (ref "IC1") (pin "55") (pinfunction "PB3_55") (pintype "bidirectional"))
    )
    (net (code "69") (name "unconnected-(IC1-PB4-Pad56)") (class "Default")
      (node (ref "IC1") (pin "56") (pinfunction "PB4_56") (pintype "bidirectional"))
    )
    (net (code "70") (name "unconnected-(IC1-PB5-Pad57)") (class "Default")
      (node (ref "IC1") (pin "57") (pinfunction "PB5_57") (pintype "bidirectional"))
    )
    (net (code "71") (name "unconnected-(IC1-PB6-Pad58)") (class "Default")
      (node (ref "IC1") (pin "58") (pinfunction "PB6_58") (pintype "bidirectional"))
    )
    (net (code "72") (name "unconnected-(IC1-PB7-Pad59)") (class "Default")
      (node (ref "IC1") (pin "59") (pinfunction "PB7_59") (pintype "bidirectional"))
    )
    (net (code "73") (name "unconnected-(IC1-PB8-Pad61)") (class "Default")
      (node (ref "IC1") (pin "61") (pinfunction "PB8_61") (pintype "bidirectional"))
    )
    (net (code "74") (name "unconnected-(IC1-PB9-Pad62)") (class "Default")
      (node (ref "IC1") (pin "62") (pinfunction "PB9_62") (pintype "bidirectional"))
    )
    (net (code "75") (name "unconnected-(IC1-PB15-Pad36)") (class "Default")
      (node (ref "IC1") (pin "36") (pinfunction "PB15_36") (pintype "bidirectional"))
    )
    (net (code "76") (name "unconnected-(IC1-PC4-Pad24)") (class "Default")
      (node (ref "IC1") (pin "24") (pinfunction "PC4_24") (pintype "bidirectional"))
    )
    (net (code "77") (name "unconnected-(IC1-PC5-Pad25)") (class "Default")
      (node (ref "IC1") (pin "25") (pinfunction "PC5_25") (pintype "bidirectional"))
    )
    (net (code "78") (name "unconnected-(IC1-PC6-Pad37)") (class "Default")
      (node (ref "IC1") (pin "37") (pinfunction "PC6_37") (pintype "bidirectional"))
    )
    (net (code "79") (name "unconnected-(IC1-PC7-Pad38)") (class "Default")
      (node (ref "IC1") (pin "38") (pinfunction "PC7_38") (pintype "bidirectional"))
    )
    (net (code "80") (name "unconnected-(IC1-PC8-Pad39)") (class "Default")
      (node (ref "IC1") (pin "39") (pinfunction "PC8_39") (pintype "bidirectional"))
    )
    (net (code "81") (name "unconnected-(IC1-PC9-Pad40)") (class "Default")
      (node (ref "IC1") (pin "40") (pinfunction "PC9_40") (pintype "bidirectional"))
    )
    (net (code "82") (name "unconnected-(IC1-PC12-Pad53)") (class "Default")
      (node (ref "IC1") (pin "53") (pinfunction "PC12_53") (pintype "bidirectional"))
    )
    (net (code "83") (name "unconnected-(IC1-PC13-TAMPER-RTC-Pad2)") (class "Default")
      (node (ref "IC1") (pin "2") (pinfunction "PC13-TAMPER-RTC_2") (pintype "bidirectional"))
    )
    (net (code "84") (name "unconnected-(IC1-PC14-OSC32_IN-Pad3)") (class "Default")
      (node (ref "IC1") (pin "3") (pinfunction "PC14-OSC32_IN_3") (pintype "bidirectional"))
    )
    (net (code "85") (name "unconnected-(IC1-PC15-OSC32_OUT-Pad4)") (class "Default")
      (node (ref "IC1") (pin "4") (pinfunction "PC15-OSC32_OUT_4") (pintype "bidirectional"))
    )
    (net (code "86") (name "unconnected-(IC1-PD2-Pad54)") (class "Default")
      (node (ref "IC1") (pin "54") (pinfunction "PD2_54") (pintype "bidirectional"))
    )
    (net (code "87") (name "unconnected-(IC1-VBAT-Pad1)") (class "Default")
      (node (ref "IC1") (pin "1") (pinfunction "VBAT_1") (pintype "bidirectional"))
    )
    (net (code "88") (name "unconnected-(X2-ID-Pad4)") (class "Default")
      (node (ref "X2") (pin "4") (pinfunction "ID_4") (pintype "passive"))
    )
    (net (code "89") (name "unconnected-(X3-GND-PadP$2)") (class "Default")
      (node (ref "X3") (pin "P$2") (pinfunction "GND_P$2") (pintype "bidirectional"))
    )
  )
)
